# FPGA_IO.net
KiCad netlist of a schematic drawn in Altium Designer
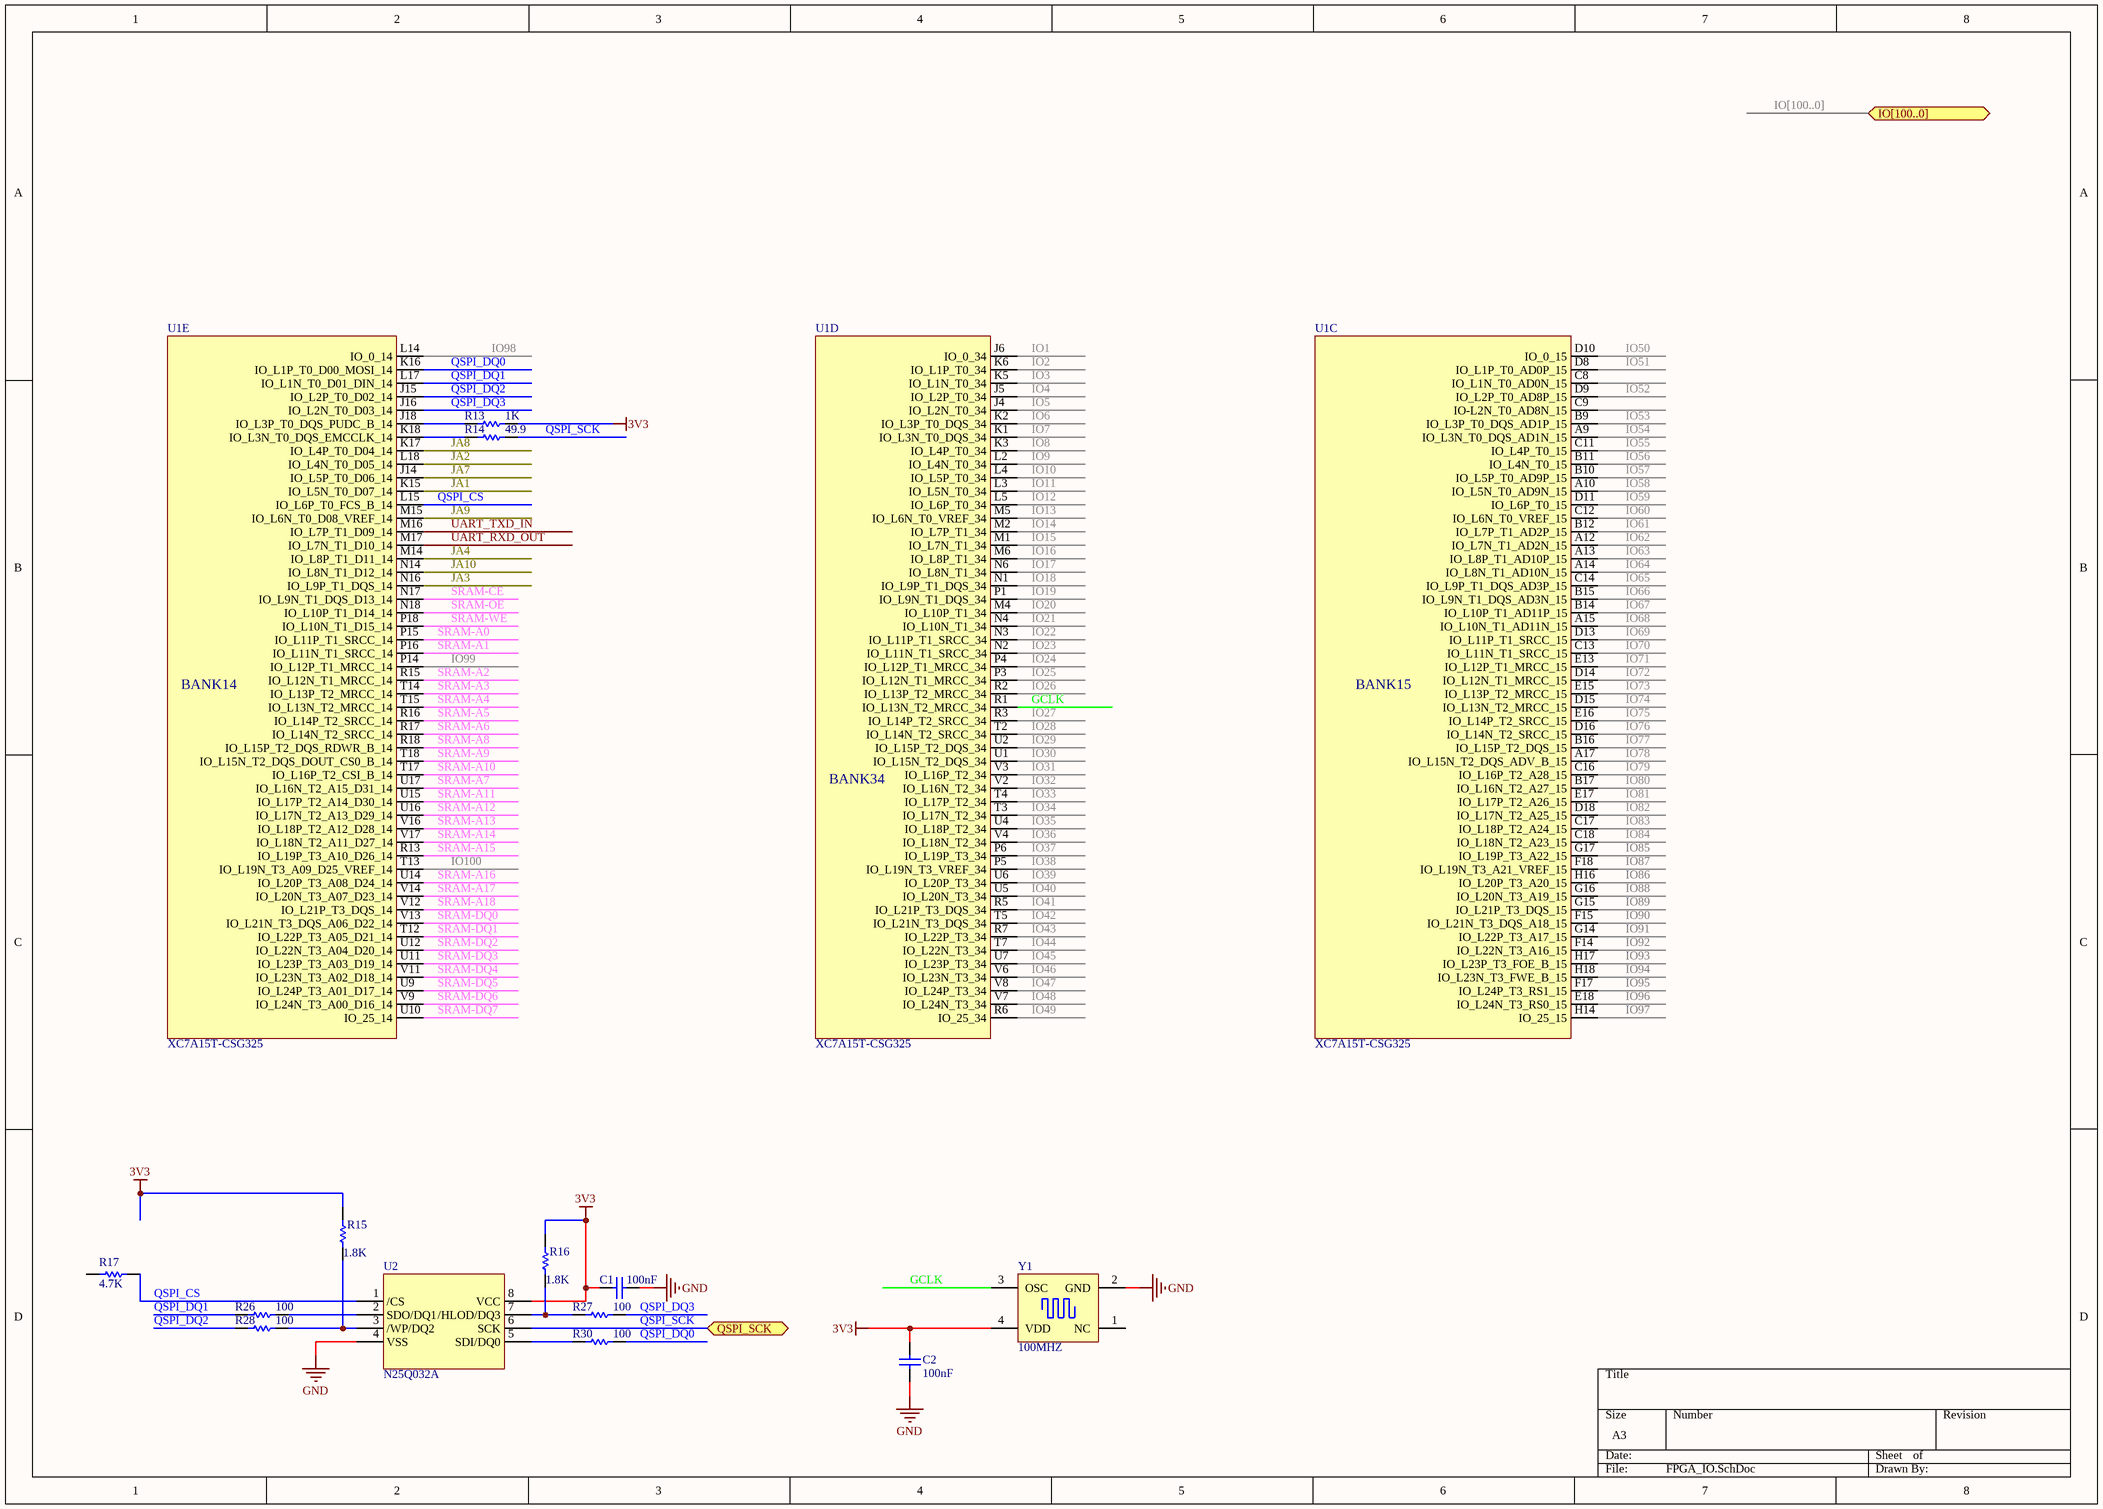
[diagram p0: FPGA_IO.SchDoc]

(export (version "E")
  (design (tool "Eeschema 10.0.6"))
  (components
    (comp (ref "C1")
      (value "100nF")
      (footprint "C2012")
      (description "贴片电容")
      (fields (field (name "Comment") "Cap") (field (name "PUBLISHER") "Altium Limited"))
      (libsource (lib "Sparks") (part "Cap"))
    )
    (comp (ref "C2")
      (value "100nF")
      (footprint "C2012")
      (description "贴片电容")
      (fields (field (name "Comment") "Cap") (field (name "PUBLISHER") "Altium Limited"))
      (libsource (lib "Sparks") (part "Cap"))
    )
    (comp (ref "R13")
      (value "1K")
      (footprint "R2012")
      (description "贴片电阻")
      (fields (field (name "Comment") "Res") (field (name "PUBLISHER") "Altium Limited"))
      (libsource (lib "Sparks") (part "Res"))
    )
    (comp (ref "R14")
      (value "49.9")
      (footprint "R2012")
      (description "贴片电阻")
      (fields (field (name "Comment") "Res") (field (name "PUBLISHER") "Altium Limited"))
      (libsource (lib "Sparks") (part "Res"))
    )
    (comp (ref "R15")
      (value "1.8K")
      (footprint "R2012")
      (description "贴片电阻")
      (fields (field (name "Comment") "Res") (field (name "PUBLISHER") "Altium Limited"))
      (libsource (lib "Sparks") (part "Res"))
    )
    (comp (ref "R16")
      (value "1.8K")
      (footprint "R2012")
      (description "贴片电阻")
      (fields (field (name "Comment") "Res") (field (name "PUBLISHER") "Altium Limited"))
      (libsource (lib "Sparks") (part "Res"))
    )
    (comp (ref "R17")
      (value "4.7K")
      (footprint "R2012")
      (description "贴片电阻")
      (fields (field (name "Comment") "Res") (field (name "PUBLISHER") "Altium Limited"))
      (libsource (lib "Sparks") (part "Res"))
    )
    (comp (ref "R26")
      (value "100")
      (footprint "R2012")
      (description "贴片电阻")
      (fields (field (name "Comment") "Res") (field (name "PUBLISHER") "Altium Limited"))
      (libsource (lib "Sparks") (part "Res"))
    )
    (comp (ref "R27")
      (value "100")
      (footprint "R2012")
      (description "贴片电阻")
      (fields (field (name "Comment") "Res") (field (name "PUBLISHER") "Altium Limited"))
      (libsource (lib "Sparks") (part "Res"))
    )
    (comp (ref "R28")
      (value "100")
      (footprint "R2012")
      (description "贴片电阻")
      (fields (field (name "Comment") "Res") (field (name "PUBLISHER") "Altium Limited"))
      (libsource (lib "Sparks") (part "Res"))
    )
    (comp (ref "R30")
      (value "100")
      (footprint "R2012")
      (description "贴片电阻")
      (fields (field (name "Comment") "Res") (field (name "PUBLISHER") "Altium Limited"))
      (libsource (lib "Sparks") (part "Res"))
    )
    (comp (ref "U1")
      (value "XC7A15T-CSG325")
      (footprint "BGA100P9X9-81A")
      (description "Artix-7")
      (libsource (lib "2号库") (part "XC7A15T-CSG325"))
    )
    (comp (ref "U2") (value "N25Q032A") (libsource (lib "2号库") (part "N25Q032A")))
    (comp (ref "Y1") (value "100MHZ") (footprint "XTAL7_3225") (libsource (lib "K60-V4.0") (part "XTAL1")))
  )
  (nets
    (net (code "2") (name "/GCLK") (class "Default")
      (node (ref "U1") (pin "R1") (pinfunction "IO_L13N_T2_MRCC_34_R1") (pintype "passive"))
      (node (ref "Y1") (pin "3") (pinfunction "OSC_3") (pintype "passive"))
    )
    (net (code "3") (name "/IO1") (class "Default")
      (node (ref "U1") (pin "J6") (pinfunction "IO_0_34_J6") (pintype "passive"))
    )
    (net (code "4") (name "/IO2") (class "Default")
      (node (ref "U1") (pin "K6") (pinfunction "IO_L1P_T0_34_K6") (pintype "passive"))
    )
    (net (code "5") (name "/IO3") (class "Default")
      (node (ref "U1") (pin "K5") (pinfunction "IO_L1N_T0_34_K5") (pintype "passive"))
    )
    (net (code "6") (name "/IO4") (class "Default")
      (node (ref "U1") (pin "J5") (pinfunction "IO_L2P_T0_34_J5") (pintype "passive"))
    )
    (net (code "7") (name "/IO5") (class "Default")
      (node (ref "U1") (pin "J4") (pinfunction "IO_L2N_T0_34_J4") (pintype "passive"))
    )
    (net (code "8") (name "/IO6") (class "Default")
      (node (ref "U1") (pin "K2") (pinfunction "IO_L3P_T0_DQS_34_K2") (pintype "passive"))
    )
    (net (code "9") (name "/IO7") (class "Default")
      (node (ref "U1") (pin "K1") (pinfunction "IO_L3N_T0_DQS_34_K1") (pintype "passive"))
    )
    (net (code "10") (name "/IO8") (class "Default")
      (node (ref "U1") (pin "K3") (pinfunction "IO_L4P_T0_34_K3") (pintype "passive"))
    )
    (net (code "11") (name "/IO9") (class "Default")
      (node (ref "U1") (pin "L2") (pinfunction "IO_L4N_T0_34_L2") (pintype "passive"))
    )
    (net (code "12") (name "/IO10") (class "Default")
      (node (ref "U1") (pin "L4") (pinfunction "IO_L5P_T0_34_L4") (pintype "passive"))
    )
    (net (code "13") (name "/IO11") (class "Default")
      (node (ref "U1") (pin "L3") (pinfunction "IO_L5N_T0_34_L3") (pintype "passive"))
    )
    (net (code "14") (name "/IO12") (class "Default")
      (node (ref "U1") (pin "L5") (pinfunction "IO_L6P_T0_34_L5") (pintype "passive"))
    )
    (net (code "15") (name "/IO13") (class "Default")
      (node (ref "U1") (pin "M5") (pinfunction "IO_L6N_T0_VREF_34_M5") (pintype "passive"))
    )
    (net (code "16") (name "/IO14") (class "Default")
      (node (ref "U1") (pin "M2") (pinfunction "IO_L7P_T1_34_M2") (pintype "passive"))
    )
    (net (code "17") (name "/IO15") (class "Default")
      (node (ref "U1") (pin "M1") (pinfunction "IO_L7N_T1_34_M1") (pintype "passive"))
    )
    (net (code "18") (name "/IO16") (class "Default")
      (node (ref "U1") (pin "M6") (pinfunction "IO_L8P_T1_34_M6") (pintype "passive"))
    )
    (net (code "19") (name "/IO17") (class "Default")
      (node (ref "U1") (pin "N6") (pinfunction "IO_L8N_T1_34_N6") (pintype "passive"))
    )
    (net (code "20") (name "/IO18") (class "Default")
      (node (ref "U1") (pin "N1") (pinfunction "IO_L9P_T1_DQS_34_N1") (pintype "passive"))
    )
    (net (code "21") (name "/IO19") (class "Default")
      (node (ref "U1") (pin "P1") (pinfunction "IO_L9N_T1_DQS_34_P1") (pintype "passive"))
    )
    (net (code "22") (name "/IO20") (class "Default")
      (node (ref "U1") (pin "M4") (pinfunction "IO_L10P_T1_34_M4") (pintype "passive"))
    )
    (net (code "23") (name "/IO21") (class "Default")
      (node (ref "U1") (pin "N4") (pinfunction "IO_L10N_T1_34_N4") (pintype "passive"))
    )
    (net (code "24") (name "/IO22") (class "Default")
      (node (ref "U1") (pin "N3") (pinfunction "IO_L11P_T1_SRCC_34_N3") (pintype "passive"))
    )
    (net (code "25") (name "/IO23") (class "Default")
      (node (ref "U1") (pin "N2") (pinfunction "IO_L11N_T1_SRCC_34_N2") (pintype "passive"))
    )
    (net (code "26") (name "/IO24") (class "Default")
      (node (ref "U1") (pin "P4") (pinfunction "IO_L12P_T1_MRCC_34_P4") (pintype "passive"))
    )
    (net (code "27") (name "/IO25") (class "Default")
      (node (ref "U1") (pin "P3") (pinfunction "IO_L12N_T1_MRCC_34_P3") (pintype "passive"))
    )
    (net (code "28") (name "/IO26") (class "Default")
      (node (ref "U1") (pin "R2") (pinfunction "IO_L13P_T2_MRCC_34_R2") (pintype "passive"))
    )
    (net (code "29") (name "/IO27") (class "Default")
      (node (ref "U1") (pin "R3") (pinfunction "IO_L14P_T2_SRCC_34_R3") (pintype "passive"))
    )
    (net (code "30") (name "/IO28") (class "Default")
      (node (ref "U1") (pin "T2") (pinfunction "IO_L14N_T2_SRCC_34_T2") (pintype "passive"))
    )
    (net (code "31") (name "/IO29") (class "Default")
      (node (ref "U1") (pin "U2") (pinfunction "IO_L15P_T2_DQS_34_U2") (pintype "passive"))
    )
    (net (code "32") (name "/IO30") (class "Default")
      (node (ref "U1") (pin "U1") (pinfunction "IO_L15N_T2_DQS_34_U1") (pintype "passive"))
    )
    (net (code "33") (name "/IO31") (class "Default")
      (node (ref "U1") (pin "V3") (pinfunction "IO_L16P_T2_34_V3") (pintype "passive"))
    )
    (net (code "34") (name "/IO32") (class "Default")
      (node (ref "U1") (pin "V2") (pinfunction "IO_L16N_T2_34_V2") (pintype "passive"))
    )
    (net (code "35") (name "/IO33") (class "Default")
      (node (ref "U1") (pin "T4") (pinfunction "IO_L17P_T2_34_T4") (pintype "passive"))
    )
    (net (code "36") (name "/IO34") (class "Default")
      (node (ref "U1") (pin "T3") (pinfunction "IO_L17N_T2_34_T3") (pintype "passive"))
    )
    (net (code "37") (name "/IO35") (class "Default")
      (node (ref "U1") (pin "U4") (pinfunction "IO_L18P_T2_34_U4") (pintype "passive"))
    )
    (net (code "38") (name "/IO36") (class "Default")
      (node (ref "U1") (pin "V4") (pinfunction "IO_L18N_T2_34_V4") (pintype "passive"))
    )
    (net (code "39") (name "/IO37") (class "Default")
      (node (ref "U1") (pin "P6") (pinfunction "IO_L19P_T3_34_P6") (pintype "passive"))
    )
    (net (code "40") (name "/IO38") (class "Default")
      (node (ref "U1") (pin "P5") (pinfunction "IO_L19N_T3_VREF_34_P5") (pintype "passive"))
    )
    (net (code "41") (name "/IO39") (class "Default")
      (node (ref "U1") (pin "U6") (pinfunction "IO_L20P_T3_34_U6") (pintype "passive"))
    )
    (net (code "42") (name "/IO40") (class "Default")
      (node (ref "U1") (pin "U5") (pinfunction "IO_L20N_T3_34_U5") (pintype "passive"))
    )
    (net (code "43") (name "/IO41") (class "Default")
      (node (ref "U1") (pin "R5") (pinfunction "IO_L21P_T3_DQS_34_R5") (pintype "passive"))
    )
    (net (code "44") (name "/IO42") (class "Default")
      (node (ref "U1") (pin "T5") (pinfunction "IO_L21N_T3_DQS_34_T5") (pintype "passive"))
    )
    (net (code "45") (name "/IO43") (class "Default")
      (node (ref "U1") (pin "R7") (pinfunction "IO_L22P_T3_34_R7") (pintype "passive"))
    )
    (net (code "46") (name "/IO44") (class "Default")
      (node (ref "U1") (pin "T7") (pinfunction "IO_L22N_T3_34_T7") (pintype "passive"))
    )
    (net (code "47") (name "/IO45") (class "Default")
      (node (ref "U1") (pin "U7") (pinfunction "IO_L23P_T3_34_U7") (pintype "passive"))
    )
    (net (code "48") (name "/IO46") (class "Default")
      (node (ref "U1") (pin "V6") (pinfunction "IO_L23N_T3_34_V6") (pintype "passive"))
    )
    (net (code "49") (name "/IO47") (class "Default")
      (node (ref "U1") (pin "V8") (pinfunction "IO_L24P_T3_34_V8") (pintype "passive"))
    )
    (net (code "50") (name "/IO48") (class "Default")
      (node (ref "U1") (pin "V7") (pinfunction "IO_L24N_T3_34_V7") (pintype "passive"))
    )
    (net (code "51") (name "/IO49") (class "Default")
      (node (ref "U1") (pin "R6") (pinfunction "IO_25_34_R6") (pintype "passive"))
    )
    (net (code "52") (name "/IO50") (class "Default")
      (node (ref "U1") (pin "D10") (pinfunction "IO_0_15_D10") (pintype "passive"))
    )
    (net (code "53") (name "/IO51") (class "Default")
      (node (ref "U1") (pin "D8") (pinfunction "IO_L1P_T0_AD0P_15_D8") (pintype "passive"))
    )
    (net (code "54") (name "/IO52") (class "Default")
      (node (ref "U1") (pin "D9") (pinfunction "IO_L2P_T0_AD8P_15_D9") (pintype "passive"))
    )
    (net (code "55") (name "/IO53") (class "Default")
      (node (ref "U1") (pin "B9") (pinfunction "IO_L3P_T0_DQS_AD1P_15_B9") (pintype "passive"))
    )
    (net (code "56") (name "/IO54") (class "Default")
      (node (ref "U1") (pin "A9") (pinfunction "IO_L3N_T0_DQS_AD1N_15_A9") (pintype "passive"))
    )
    (net (code "57") (name "/IO55") (class "Default")
      (node (ref "U1") (pin "C11") (pinfunction "IO_L4P_T0_15_C11") (pintype "passive"))
    )
    (net (code "58") (name "/IO56") (class "Default")
      (node (ref "U1") (pin "B11") (pinfunction "IO_L4N_T0_15_B11") (pintype "passive"))
    )
    (net (code "59") (name "/IO57") (class "Default")
      (node (ref "U1") (pin "B10") (pinfunction "IO_L5P_T0_AD9P_15_B10") (pintype "passive"))
    )
    (net (code "60") (name "/IO58") (class "Default")
      (node (ref "U1") (pin "A10") (pinfunction "IO_L5N_T0_AD9N_15_A10") (pintype "passive"))
    )
    (net (code "61") (name "/IO59") (class "Default")
      (node (ref "U1") (pin "D11") (pinfunction "IO_L6P_T0_15_D11") (pintype "passive"))
    )
    (net (code "62") (name "/IO60") (class "Default")
      (node (ref "U1") (pin "C12") (pinfunction "IO_L6N_T0_VREF_15_C12") (pintype "passive"))
    )
    (net (code "63") (name "/IO61") (class "Default")
      (node (ref "U1") (pin "B12") (pinfunction "IO_L7P_T1_AD2P_15_B12") (pintype "passive"))
    )
    (net (code "64") (name "/IO62") (class "Default")
      (node (ref "U1") (pin "A12") (pinfunction "IO_L7N_T1_AD2N_15_A12") (pintype "passive"))
    )
    (net (code "65") (name "/IO63") (class "Default")
      (node (ref "U1") (pin "A13") (pinfunction "IO_L8P_T1_AD10P_15_A13") (pintype "passive"))
    )
    (net (code "66") (name "/IO64") (class "Default")
      (node (ref "U1") (pin "A14") (pinfunction "IO_L8N_T1_AD10N_15_A14") (pintype "passive"))
    )
    (net (code "67") (name "/IO65") (class "Default")
      (node (ref "U1") (pin "C14") (pinfunction "IO_L9P_T1_DQS_AD3P_15_C14") (pintype "passive"))
    )
    (net (code "68") (name "/IO66") (class "Default")
      (node (ref "U1") (pin "B15") (pinfunction "IO_L9N_T1_DQS_AD3N_15_B15") (pintype "passive"))
    )
    (net (code "69") (name "/IO67") (class "Default")
      (node (ref "U1") (pin "B14") (pinfunction "IO_L10P_T1_AD11P_15_B14") (pintype "passive"))
    )
    (net (code "70") (name "/IO68") (class "Default")
      (node (ref "U1") (pin "A15") (pinfunction "IO_L10N_T1_AD11N_15_A15") (pintype "passive"))
    )
    (net (code "71") (name "/IO69") (class "Default")
      (node (ref "U1") (pin "D13") (pinfunction "IO_L11P_T1_SRCC_15_D13") (pintype "passive"))
    )
    (net (code "72") (name "/IO70") (class "Default")
      (node (ref "U1") (pin "C13") (pinfunction "IO_L11N_T1_SRCC_15_C13") (pintype "passive"))
    )
    (net (code "73") (name "/IO71") (class "Default")
      (node (ref "U1") (pin "E13") (pinfunction "IO_L12P_T1_MRCC_15_E13") (pintype "passive"))
    )
    (net (code "74") (name "/IO72") (class "Default")
      (node (ref "U1") (pin "D14") (pinfunction "IO_L12N_T1_MRCC_15_D14") (pintype "passive"))
    )
    (net (code "75") (name "/IO73") (class "Default")
      (node (ref "U1") (pin "E15") (pinfunction "IO_L13P_T2_MRCC_15_E15") (pintype "passive"))
    )
    (net (code "76") (name "/IO74") (class "Default")
      (node (ref "U1") (pin "D15") (pinfunction "IO_L13N_T2_MRCC_15_D15") (pintype "passive"))
    )
    (net (code "77") (name "/IO75") (class "Default")
      (node (ref "U1") (pin "E16") (pinfunction "IO_L14P_T2_SRCC_15_E16") (pintype "passive"))
    )
    (net (code "78") (name "/IO76") (class "Default")
      (node (ref "U1") (pin "D16") (pinfunction "IO_L14N_T2_SRCC_15_D16") (pintype "passive"))
    )
    (net (code "79") (name "/IO77") (class "Default")
      (node (ref "U1") (pin "B16") (pinfunction "IO_L15P_T2_DQS_15_B16") (pintype "passive"))
    )
    (net (code "80") (name "/IO78") (class "Default")
      (node (ref "U1") (pin "A17") (pinfunction "IO_L15N_T2_DQS_ADV_B_15_A17") (pintype "passive"))
    )
    (net (code "81") (name "/IO79") (class "Default")
      (node (ref "U1") (pin "C16") (pinfunction "IO_L16P_T2_A28_15_C16") (pintype "passive"))
    )
    (net (code "82") (name "/IO80") (class "Default")
      (node (ref "U1") (pin "B17") (pinfunction "IO_L16N_T2_A27_15_B17") (pintype "passive"))
    )
    (net (code "83") (name "/IO81") (class "Default")
      (node (ref "U1") (pin "E17") (pinfunction "IO_L17P_T2_A26_15_E17") (pintype "passive"))
    )
    (net (code "84") (name "/IO82") (class "Default")
      (node (ref "U1") (pin "D18") (pinfunction "IO_L17N_T2_A25_15_D18") (pintype "passive"))
    )
    (net (code "85") (name "/IO83") (class "Default")
      (node (ref "U1") (pin "C17") (pinfunction "IO_L18P_T2_A24_15_C17") (pintype "passive"))
    )
    (net (code "86") (name "/IO84") (class "Default")
      (node (ref "U1") (pin "C18") (pinfunction "IO_L18N_T2_A23_15_C18") (pintype "passive"))
    )
    (net (code "87") (name "/IO85") (class "Default")
      (node (ref "U1") (pin "G17") (pinfunction "IO_L19P_T3_A22_15_G17") (pintype "passive"))
    )
    (net (code "88") (name "/IO86") (class "Default")
      (node (ref "U1") (pin "H16") (pinfunction "IO_L20P_T3_A20_15_H16") (pintype "passive"))
    )
    (net (code "89") (name "/IO87") (class "Default")
      (node (ref "U1") (pin "F18") (pinfunction "IO_L19N_T3_A21_VREF_15_F18") (pintype "passive"))
    )
    (net (code "90") (name "/IO88") (class "Default")
      (node (ref "U1") (pin "G16") (pinfunction "IO_L20N_T3_A19_15_G16") (pintype "passive"))
    )
    (net (code "91") (name "/IO89") (class "Default")
      (node (ref "U1") (pin "G15") (pinfunction "IO_L21P_T3_DQS_15_G15") (pintype "passive"))
    )
    (net (code "92") (name "/IO90") (class "Default")
      (node (ref "U1") (pin "F15") (pinfunction "IO_L21N_T3_DQS_A18_15_F15") (pintype "passive"))
    )
    (net (code "93") (name "/IO91") (class "Default")
      (node (ref "U1") (pin "G14") (pinfunction "IO_L22P_T3_A17_15_G14") (pintype "passive"))
    )
    (net (code "94") (name "/IO92") (class "Default")
      (node (ref "U1") (pin "F14") (pinfunction "IO_L22N_T3_A16_15_F14") (pintype "passive"))
    )
    (net (code "95") (name "/IO93") (class "Default")
      (node (ref "U1") (pin "H17") (pinfunction "IO_L23P_T3_FOE_B_15_H17") (pintype "passive"))
    )
    (net (code "96") (name "/IO94") (class "Default")
      (node (ref "U1") (pin "H18") (pinfunction "IO_L23N_T3_FWE_B_15_H18") (pintype "passive"))
    )
    (net (code "97") (name "/IO95") (class "Default")
      (node (ref "U1") (pin "F17") (pinfunction "IO_L24P_T3_RS1_15_F17") (pintype "passive"))
    )
    (net (code "98") (name "/IO96") (class "Default")
      (node (ref "U1") (pin "E18") (pinfunction "IO_L24N_T3_RS0_15_E18") (pintype "passive"))
    )
    (net (code "99") (name "/IO97") (class "Default")
      (node (ref "U1") (pin "H14") (pinfunction "IO_25_15_H14") (pintype "passive"))
    )
    (net (code "100") (name "/IO98") (class "Default")
      (node (ref "U1") (pin "L14") (pinfunction "IO_0_14_L14") (pintype "passive"))
    )
    (net (code "101") (name "/IO99") (class "Default")
      (node (ref "U1") (pin "P14") (pinfunction "IO_L12P_T1_MRCC_14_P14") (pintype "passive"))
    )
    (net (code "102") (name "/IO100") (class "Default")
      (node (ref "U1") (pin "T13") (pinfunction "IO_L19N_T3_A09_D25_VREF_14_T13") (pintype "passive"))
    )
    (net (code "104") (name "/JA1") (class "Default")
      (node (ref "U1") (pin "K15") (pinfunction "IO_L5N_T0_D07_14_K15") (pintype "passive"))
    )
    (net (code "105") (name "/JA2") (class "Default")
      (node (ref "U1") (pin "L18") (pinfunction "IO_L4N_T0_D05_14_L18") (pintype "passive"))
    )
    (net (code "106") (name "/JA3") (class "Default")
      (node (ref "U1") (pin "N16") (pinfunction "IO_L9P_T1_DQS_14_N16") (pintype "passive"))
    )
    (net (code "107") (name "/JA4") (class "Default")
      (node (ref "U1") (pin "M14") (pinfunction "IO_L8P_T1_D11_14_M14") (pintype "passive"))
    )
    (net (code "108") (name "/JA7") (class "Default")
      (node (ref "U1") (pin "J14") (pinfunction "IO_L5P_T0_D06_14_J14") (pintype "passive"))
    )
    (net (code "109") (name "/JA8") (class "Default")
      (node (ref "U1") (pin "K17") (pinfunction "IO_L4P_T0_D04_14_K17") (pintype "passive"))
    )
    (net (code "110") (name "/JA9") (class "Default")
      (node (ref "U1") (pin "M15") (pinfunction "IO_L6N_T0_D08_VREF_14_M15") (pintype "passive"))
    )
    (net (code "111") (name "/JA10") (class "Default")
      (node (ref "U1") (pin "N14") (pinfunction "IO_L8N_T1_D12_14_N14") (pintype "passive"))
    )
    (net (code "112") (name "/QSPI_CS") (class "Default")
      (node (ref "R17") (pin "1") (pinfunction "1_1") (pintype "passive"))
      (node (ref "U1") (pin "L15") (pinfunction "IO_L6P_T0_FCS_B_14_L15") (pintype "passive"))
      (node (ref "U2") (pin "1") (pinfunction "/CS_1") (pintype "passive"))
    )
    (net (code "113") (name "/QSPI_DQ0") (class "Default")
      (node (ref "R30") (pin "1") (pinfunction "1_1") (pintype "passive"))
      (node (ref "U1") (pin "K16") (pinfunction "IO_L1P_T0_D00_MOSI_14_K16") (pintype "passive"))
    )
    (net (code "114") (name "/QSPI_DQ1") (class "Default")
      (node (ref "R26") (pin "2") (pinfunction "2_2") (pintype "passive"))
      (node (ref "U1") (pin "L17") (pinfunction "IO_L1N_T0_D01_DIN_14_L17") (pintype "passive"))
    )
    (net (code "115") (name "/QSPI_DQ2") (class "Default")
      (node (ref "R28") (pin "2") (pinfunction "2_2") (pintype "passive"))
      (node (ref "U1") (pin "J15") (pinfunction "IO_L2P_T0_D02_14_J15") (pintype "passive"))
    )
    (net (code "116") (name "/QSPI_DQ3") (class "Default")
      (node (ref "R27") (pin "1") (pinfunction "1_1") (pintype "passive"))
      (node (ref "U1") (pin "J16") (pinfunction "IO_L2N_T0_D03_14_J16") (pintype "passive"))
    )
    (net (code "117") (name "/QSPI_SCK") (class "Default")
      (node (ref "R14") (pin "1") (pinfunction "1_1") (pintype "passive"))
      (node (ref "U2") (pin "6") (pinfunction "SCK_6") (pintype "passive"))
    )
    (net (code "118") (name "/SRAM-A0") (class "Default")
      (node (ref "U1") (pin "P15") (pinfunction "IO_L11P_T1_SRCC_14_P15") (pintype "passive"))
    )
    (net (code "119") (name "/SRAM-A1") (class "Default")
      (node (ref "U1") (pin "P16") (pinfunction "IO_L11N_T1_SRCC_14_P16") (pintype "passive"))
    )
    (net (code "120") (name "/SRAM-A2") (class "Default")
      (node (ref "U1") (pin "R15") (pinfunction "IO_L12N_T1_MRCC_14_R15") (pintype "passive"))
    )
    (net (code "121") (name "/SRAM-A3") (class "Default")
      (node (ref "U1") (pin "T14") (pinfunction "IO_L13P_T2_MRCC_14_T14") (pintype "passive"))
    )
    (net (code "122") (name "/SRAM-A4") (class "Default")
      (node (ref "U1") (pin "T15") (pinfunction "IO_L13N_T2_MRCC_14_T15") (pintype "passive"))
    )
    (net (code "123") (name "/SRAM-A5") (class "Default")
      (node (ref "U1") (pin "R16") (pinfunction "IO_L14P_T2_SRCC_14_R16") (pintype "passive"))
    )
    (net (code "124") (name "/SRAM-A6") (class "Default")
      (node (ref "U1") (pin "R17") (pinfunction "IO_L14N_T2_SRCC_14_R17") (pintype "passive"))
    )
    (net (code "125") (name "/SRAM-A7") (class "Default")
      (node (ref "U1") (pin "U17") (pinfunction "IO_L16N_T2_A15_D31_14_U17") (pintype "passive"))
    )
    (net (code "126") (name "/SRAM-A8") (class "Default")
      (node (ref "U1") (pin "R18") (pinfunction "IO_L15P_T2_DQS_RDWR_B_14_R18") (pintype "passive"))
    )
    (net (code "127") (name "/SRAM-A9") (class "Default")
      (node (ref "U1") (pin "T18") (pinfunction "IO_L15N_T2_DQS_DOUT_CS0_B_14_T18") (pintype "passive"))
    )
    (net (code "128") (name "/SRAM-A10") (class "Default")
      (node (ref "U1") (pin "T17") (pinfunction "IO_L16P_T2_CSI_B_14_T17") (pintype "passive"))
    )
    (net (code "129") (name "/SRAM-A11") (class "Default")
      (node (ref "U1") (pin "U15") (pinfunction "IO_L17P_T2_A14_D30_14_U15") (pintype "passive"))
    )
    (net (code "130") (name "/SRAM-A12") (class "Default")
      (node (ref "U1") (pin "U16") (pinfunction "IO_L17N_T2_A13_D29_14_U16") (pintype "passive"))
    )
    (net (code "131") (name "/SRAM-A13") (class "Default")
      (node (ref "U1") (pin "V16") (pinfunction "IO_L18P_T2_A12_D28_14_V16") (pintype "passive"))
    )
    (net (code "132") (name "/SRAM-A14") (class "Default")
      (node (ref "U1") (pin "V17") (pinfunction "IO_L18N_T2_A11_D27_14_V17") (pintype "passive"))
    )
    (net (code "133") (name "/SRAM-A15") (class "Default")
      (node (ref "U1") (pin "R13") (pinfunction "IO_L19P_T3_A10_D26_14_R13") (pintype "passive"))
    )
    (net (code "134") (name "/SRAM-A16") (class "Default")
      (node (ref "U1") (pin "U14") (pinfunction "IO_L20P_T3_A08_D24_14_U14") (pintype "passive"))
    )
    (net (code "135") (name "/SRAM-A17") (class "Default")
      (node (ref "U1") (pin "V14") (pinfunction "IO_L20N_T3_A07_D23_14_V14") (pintype "passive"))
    )
    (net (code "136") (name "/SRAM-A18") (class "Default")
      (node (ref "U1") (pin "V12") (pinfunction "IO_L21P_T3_DQS_14_V12") (pintype "passive"))
    )
    (net (code "137") (name "/SRAM-CE") (class "Default")
      (node (ref "U1") (pin "N17") (pinfunction "IO_L9N_T1_DQS_D13_14_N17") (pintype "passive"))
    )
    (net (code "138") (name "/SRAM-DQ0") (class "Default")
      (node (ref "U1") (pin "V13") (pinfunction "IO_L21N_T3_DQS_A06_D22_14_V13") (pintype "passive"))
    )
    (net (code "139") (name "/SRAM-DQ1") (class "Default")
      (node (ref "U1") (pin "T12") (pinfunction "IO_L22P_T3_A05_D21_14_T12") (pintype "passive"))
    )
    (net (code "140") (name "/SRAM-DQ2") (class "Default")
      (node (ref "U1") (pin "U12") (pinfunction "IO_L22N_T3_A04_D20_14_U12") (pintype "passive"))
    )
    (net (code "141") (name "/SRAM-DQ3") (class "Default")
      (node (ref "U1") (pin "U11") (pinfunction "IO_L23P_T3_A03_D19_14_U11") (pintype "passive"))
    )
    (net (code "142") (name "/SRAM-DQ4") (class "Default")
      (node (ref "U1") (pin "V11") (pinfunction "IO_L23N_T3_A02_D18_14_V11") (pintype "passive"))
    )
    (net (code "143") (name "/SRAM-DQ5") (class "Default")
      (node (ref "U1") (pin "U9") (pinfunction "IO_L24P_T3_A01_D17_14_U9") (pintype "passive"))
    )
    (net (code "144") (name "/SRAM-DQ6") (class "Default")
      (node (ref "U1") (pin "V9") (pinfunction "IO_L24N_T3_A00_D16_14_V9") (pintype "passive"))
    )
    (net (code "145") (name "/SRAM-DQ7") (class "Default")
      (node (ref "U1") (pin "U10") (pinfunction "IO_25_14_U10") (pintype "passive"))
    )
    (net (code "146") (name "/SRAM-OE") (class "Default")
      (node (ref "U1") (pin "N18") (pinfunction "IO_L10P_T1_D14_14_N18") (pintype "passive"))
    )
    (net (code "147") (name "/SRAM-WE") (class "Default")
      (node (ref "U1") (pin "P18") (pinfunction "IO_L10N_T1_D15_14_P18") (pintype "passive"))
    )
    (net (code "148") (name "/UART_RXD_OUT") (class "Default")
      (node (ref "U1") (pin "M17") (pinfunction "IO_L7N_T1_D10_14_M17") (pintype "passive"))
    )
    (net (code "149") (name "/UART_TXD_IN") (class "Default")
      (node (ref "U1") (pin "M16") (pinfunction "IO_L7P_T1_D09_14_M16") (pintype "passive"))
    )
    (net (code "150") (name "3V3") (class "Default")
      (node (ref "C1") (pin "1") (pinfunction "1_1") (pintype "passive"))
      (node (ref "C2") (pin "2") (pinfunction "2_2") (pintype "passive"))
      (node (ref "R13") (pin "1") (pinfunction "1_1") (pintype "passive"))
      (node (ref "R15") (pin "1") (pinfunction "1_1") (pintype "passive"))
      (node (ref "R16") (pin "1") (pinfunction "1_1") (pintype "passive"))
      (node (ref "U2") (pin "8") (pinfunction "VCC_8") (pintype "passive"))
      (node (ref "Y1") (pin "4") (pinfunction "VDD_4") (pintype "passive"))
    )
    (net (code "151") (name "GND") (class "Default")
      (node (ref "C1") (pin "2") (pinfunction "2_2") (pintype "passive"))
      (node (ref "C2") (pin "1") (pinfunction "1_1") (pintype "passive"))
      (node (ref "U2") (pin "4") (pinfunction "VSS_4") (pintype "passive"))
      (node (ref "Y1") (pin "2") (pinfunction "GND_2") (pintype "passive"))
    )
    (net (code "152") (name "Net-(U1E-IO_L3N_T0_DQS_EMCCLK_14)") (class "Default")
      (node (ref "R14") (pin "2") (pinfunction "2_2") (pintype "passive"))
      (node (ref "U1") (pin "K18") (pinfunction "IO_L3N_T0_DQS_EMCCLK_14_K18") (pintype "passive"))
    )
    (net (code "153") (name "Net-(U1E-IO_L3P_T0_DQS_PUDC_B_14)") (class "Default")
      (node (ref "R13") (pin "2") (pinfunction "2_2") (pintype "passive"))
      (node (ref "U1") (pin "J18") (pinfunction "IO_L3P_T0_DQS_PUDC_B_14_J18") (pintype "passive"))
    )
    (net (code "154") (name "Net-(U2-SDI{slash}DQ0)") (class "Default")
      (node (ref "R30") (pin "2") (pinfunction "2_2") (pintype "passive"))
      (node (ref "U2") (pin "5") (pinfunction "SDI/DQ0_5") (pintype "passive"))
    )
    (net (code "155") (name "Net-(U2-SDO{slash}DQ1)") (class "Default")
      (node (ref "R26") (pin "1") (pinfunction "1_1") (pintype "passive"))
      (node (ref "U2") (pin "2") (pinfunction "SDO/DQ1_2") (pintype "passive"))
    )
    (net (code "156") (name "Net-(U2-{slash}HLOD{slash}DQ3)") (class "Default")
      (node (ref "R16") (pin "2") (pinfunction "2_2") (pintype "passive"))
      (node (ref "R27") (pin "2") (pinfunction "2_2") (pintype "passive"))
      (node (ref "U2") (pin "7") (pinfunction "/HLOD/DQ3_7") (pintype "passive"))
    )
    (net (code "157") (name "Net-(U2-{slash}WP{slash}DQ2)") (class "Default")
      (node (ref "R15") (pin "2") (pinfunction "2_2") (pintype "passive"))
      (node (ref "R28") (pin "1") (pinfunction "1_1") (pintype "passive"))
      (node (ref "U2") (pin "3") (pinfunction "/WP/DQ2_3") (pintype "passive"))
    )
    (net (code "158") (name "unconnected-(R17-Pad2)") (class "Default")
      (node (ref "R17") (pin "2") (pinfunction "2_2") (pintype "passive"))
    )
    (net (code "159") (name "unconnected-(U1C-IO-L2N_T0_AD8N_15-PadC9)") (class "Default")
      (node (ref "U1") (pin "C9") (pinfunction "IO-L2N_T0_AD8N_15_C9") (pintype "passive"))
    )
    (net (code "160") (name "unconnected-(U1C-IO_L1N_T0_AD0N_15-PadC8)") (class "Default")
      (node (ref "U1") (pin "C8") (pinfunction "IO_L1N_T0_AD0N_15_C8") (pintype "passive"))
    )
    (net (code "161") (name "unconnected-(Y1-NC-Pad1)") (class "Default")
      (node (ref "Y1") (pin "1") (pinfunction "NC_1") (pintype "passive"))
    )
  )
)
